# SCH001.net
KiCad netlist of a schematic drawn in Altium Designer
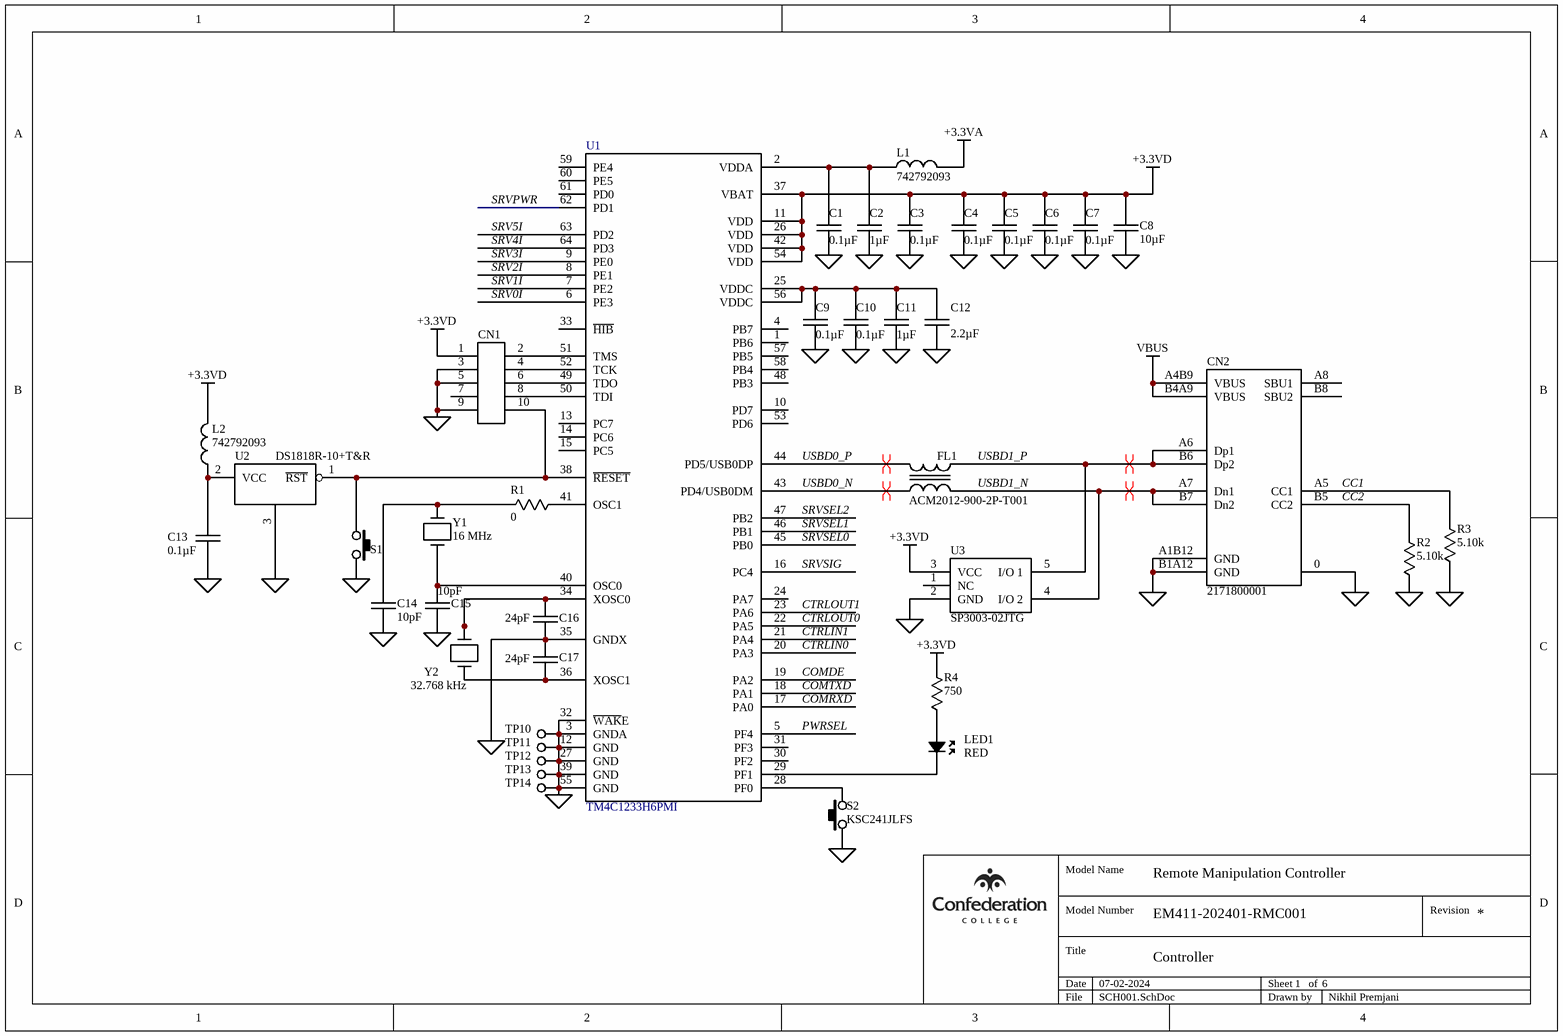
[diagram p0: SCH001.SchDoc]

(export (version "E")
  (design (tool "Eeschema 10.0.6"))
  (components
    (comp (ref "C1")
      (value "0.1µF")
      (footprint "CAPC2012X14N")
      (description "0.1µF/50V/±10% X7R Ceramic Chip Capacitor")
      (fields (field (name "MANUFACTURER") "Taiyo Yuden") (field (name "PARTNUMBER") "UMK212B7104KGHT"))
      (libsource (lib "EM411-202401-RMC001-001") (part "UMK212B7104KGHT"))
    )
    (comp (ref "C2")
      (value "1µF")
      (footprint "CAPC2012X14N")
      (description "1µF/50V/±10% X7R Ceramic Chip Capacitor")
      (fields
        (field (name "MANUFACTURER") "Samsung Electro-Mechanics")
        (field (name "PARTNUMBER") "CL21B105KBFNNNG")
      )
      (libsource (lib "EM411-202401-RMC001-001") (part "CL21B105KBFNNNG"))
    )
    (comp (ref "C3")
      (value "0.1µF")
      (footprint "CAPC2012X14N")
      (description "0.1µF/50V/±10% X7R Ceramic Chip Capacitor")
      (fields (field (name "MANUFACTURER") "Taiyo Yuden") (field (name "PARTNUMBER") "UMK212B7104KGHT"))
      (libsource (lib "EM411-202401-RMC001-001") (part "UMK212B7104KGHT"))
    )
    (comp (ref "C4")
      (value "0.1µF")
      (footprint "CAPC2012X14N")
      (description "0.1µF/50V/±10% X7R Ceramic Chip Capacitor")
      (fields (field (name "MANUFACTURER") "Taiyo Yuden") (field (name "PARTNUMBER") "UMK212B7104KGHT"))
      (libsource (lib "EM411-202401-RMC001-001") (part "UMK212B7104KGHT"))
    )
    (comp (ref "C5")
      (value "0.1µF")
      (footprint "CAPC2012X14N")
      (description "0.1µF/50V/±10% X7R Ceramic Chip Capacitor")
      (fields (field (name "MANUFACTURER") "Taiyo Yuden") (field (name "PARTNUMBER") "UMK212B7104KGHT"))
      (libsource (lib "EM411-202401-RMC001-001") (part "UMK212B7104KGHT"))
    )
    (comp (ref "C6")
      (value "0.1µF")
      (footprint "CAPC2012X14N")
      (description "0.1µF/50V/±10% X7R Ceramic Chip Capacitor")
      (fields (field (name "MANUFACTURER") "Taiyo Yuden") (field (name "PARTNUMBER") "UMK212B7104KGHT"))
      (libsource (lib "EM411-202401-RMC001-001") (part "UMK212B7104KGHT"))
    )
    (comp (ref "C7")
      (value "0.1µF")
      (footprint "CAPC2012X14N")
      (description "0.1µF/50V/±10% X7R Ceramic Chip Capacitor")
      (fields (field (name "MANUFACTURER") "Taiyo Yuden") (field (name "PARTNUMBER") "UMK212B7104KGHT"))
      (libsource (lib "EM411-202401-RMC001-001") (part "UMK212B7104KGHT"))
    )
    (comp (ref "C8")
      (value "10µF")
      (footprint "CAPC2012X14N")
      (description "10µF/25V 10% X5R Multi-Layer Ceramic Capacitor")
      (fields
        (field (name "MANUFACTURER") "Samsung Electro-Mechanics")
        (field (name "PARTNUMBER") "CL21A106KAFN3NE")
      )
      (libsource (lib "EM411-202401-RMC001-000-20240213-T10") (part "CL21A106KAFN3NE"))
    )
    (comp (ref "C9")
      (value "0.1µF")
      (footprint "CAPC2012X14N")
      (description "0.1µF/50V/±10% X7R Ceramic Chip Capacitor")
      (fields (field (name "MANUFACTURER") "Taiyo Yuden") (field (name "PARTNUMBER") "UMK212B7104KGHT"))
      (libsource (lib "EM411-202401-RMC001-001") (part "UMK212B7104KGHT"))
    )
    (comp (ref "C10")
      (value "0.1µF")
      (footprint "CAPC2012X14N")
      (description "0.1µF/50V/±10% X7R Ceramic Chip Capacitor")
      (fields (field (name "MANUFACTURER") "Taiyo Yuden") (field (name "PARTNUMBER") "UMK212B7104KGHT"))
      (libsource (lib "EM411-202401-RMC001-001") (part "UMK212B7104KGHT"))
    )
    (comp (ref "C11")
      (value "1µF")
      (footprint "CAPC2012X14N")
      (description "1µF/50V/±10% X7R Ceramic Chip Capacitor")
      (fields
        (field (name "MANUFACTURER") "Samsung Electro-Mechanics")
        (field (name "PARTNUMBER") "CL21B105KBFNNNG")
      )
      (libsource (lib "EM411-202401-RMC001-001") (part "CL21B105KBFNNNG"))
    )
    (comp (ref "C12")
      (value "2.2µF")
      (footprint "CAPC2012X14N")
      (description "2.2µF/50V/10% Multilayer Ceramic Chip Capacitor")
      (fields (field (name "MANUFACTURER") "Taiyo Yuden") (field (name "PARTNUMBER") "UMK212BB7225KG-T"))
      (libsource (lib "EM411-202401-RMC001-001") (part "UMK212BB7225KG-T"))
    )
    (comp (ref "C13")
      (value "0.1µF")
      (footprint "CAPC2012X14N")
      (description "0.1µF/50V/±10% X7R Ceramic Chip Capacitor")
      (fields (field (name "MANUFACTURER") "Taiyo Yuden") (field (name "PARTNUMBER") "UMK212B7104KGHT"))
      (libsource (lib "EM411-202401-RMC001-001") (part "UMK212B7104KGHT"))
    )
    (comp (ref "C14")
      (value "10pF")
      (footprint "CAPC2012X09N")
      (description "10pF/100V/±10% C0G (NP0) Ceramic Chip Capacitor")
      (fields (field (name "MANUFACTURER") "Kyocera/AVX") (field (name "PARTNUMBER") "08051A100KAT"))
      (libsource (lib "EM411-202401-RMC001-000-20240213-T10") (part "08051A100KAT"))
    )
    (comp (ref "C15")
      (value "10pF")
      (footprint "CAPC2012X09N")
      (description "10pF/100V/±10% C0G (NP0) Ceramic Chip Capacitor")
      (fields (field (name "MANUFACTURER") "Kyocera/AVX") (field (name "PARTNUMBER") "08051A100KAT"))
      (libsource (lib "EM411-202401-RMC001-000-20240213-T10") (part "08051A100KAT"))
    )
    (comp (ref "C16")
      (value "24pF")
      (footprint "CAPC2012X09N")
      (description "24pF/50V/±5% C0G (NP0) Ceramic Chip Capacitor")
      (fields (field (name "MANUFACTURER") "Kyocera/AVX") (field (name "PARTNUMBER") "08055A240JAT"))
      (libsource (lib "EM411-202401-RMC001-001") (part "08055A240JAT"))
    )
    (comp (ref "C17")
      (value "24pF")
      (footprint "CAPC2012X09N")
      (description "24pF/50V/±5% C0G (NP0) Ceramic Chip Capacitor")
      (fields (field (name "MANUFACTURER") "Kyocera/AVX") (field (name "PARTNUMBER") "08055A240JAT"))
      (libsource (lib "EM411-202401-RMC001-001") (part "08055A240JAT"))
    )
    (comp (ref "CN1")
      (value "GRPB052VWVN-RC")
      (footprint "SULLINS_GRPB052VWVN-RC")
      (description ".050\"[1.27mm] Contact Centers, Male Header")
      (fields (field (name "MANUFACTURER") "Sullins Connector Solutions, Inc."))
      (libsource (lib "EM411-202401-RMC001-001") (part "GRPB052VWVN-RC"))
    )
    (comp (ref "CN2")
      (value "2171800001")
      (footprint "MOLEX_2171800001")
      (fields (field (name "MANUFACTURER") "Molex"))
      (libsource (lib "EM411-202401-RMC001-000-20240213-T10") (part "2171800001"))
    )
    (comp (ref "FL1")
      (value "ACM2012-900-2P-T001")
      (footprint "LITTELFUSE_ACM2012-900-2P-T001")
      (description "Common Mode Filter")
      (fields (field (name "MANUFACTURER") "TDK"))
      (libsource (lib "EM411-202401-RMC001-000-20240213-T10") (part "ACM2012-900-2P-T001"))
    )
    (comp (ref "L1")
      (value "742792093")
      (footprint "INDC2012X11N")
      (description "Multilayer SMD Ferrite")
      (fields (field (name "MANUFACTURER") "Wurth Elektronik"))
      (libsource (lib "EM411-202401-RMC001-001") (part "742792093"))
    )
    (comp (ref "L2")
      (value "742792093")
      (footprint "INDC2012X11N")
      (description "Multilayer SMD Ferrite")
      (fields (field (name "MANUFACTURER") "Wurth Elektronik"))
      (libsource (lib "EM411-202401-RMC001-001") (part "742792093"))
    )
    (comp (ref "LED1")
      (value "RED")
      (footprint "LEDM3228X19N")
      (description "Micro LED, 597 Series, Red, SMD LED")
      (fields
        (field (name "PARTNUMBER") "597-3008-207F")
        (field (name "MANUFACTURER") "Dialight Corporation")
      )
      (libsource (lib "EM411-202401-RMC001-000-20240213-T10") (part "597-3008-207F"))
    )
    (comp (ref "R1")
      (value "0")
      (footprint "VISHAY_RESC2012X06N")
      (description "0, Jumper, Pulse Proof, High Power Thick Film Chip Resistor")
      (fields
        (field (name "MANUFACTURER") "Vishay Intertechnology")
        (field (name "PARTNUMBER") "CRCW08050000Z0EAHP")
      )
      (libsource (lib "EM411-202401-RMC001-001") (part "CRCW08050000Z0EAHP"))
    )
    (comp (ref "R2")
      (value "5.10k")
      (footprint "RESC2012X06N")
      (description "5.10k, 1%, 0.125W Thick Film Chip Resistor")
      (fields (field (name "MANUFACTURER") "Bourns") (field (name "PARTNUMBER") "CR0805-FX-4421ELF"))
      (libsource (lib "EM411-202401-RMC001-001") (part "CR0805-FX-5101ELF"))
    )
    (comp (ref "R3")
      (value "5.10k")
      (footprint "RESC2012X06N")
      (description "5.10k, 1%, 0.125W Thick Film Chip Resistor")
      (fields (field (name "MANUFACTURER") "Bourns") (field (name "PARTNUMBER") "CR0805-FX-4421ELF"))
      (libsource (lib "EM411-202401-RMC001-001") (part "CR0805-FX-5101ELF"))
    )
    (comp (ref "R4")
      (value "750")
      (footprint "RESC2012X06N")
      (description "750, 1%, 0.125W Thick Film Chip Resistor")
      (fields (field (name "MANUFACTURER") "Bourns") (field (name "PARTNUMBER") "CR0805-FX-7500ELF"))
      (libsource (lib "EM411-202401-RMC001-001") (part "CR0805-FX-7500ELF"))
    )
    (comp (ref "S1")
      (value "KSC241JLFS")
      (footprint "CK_KSC241JLFS")
      (description "KSC Series Sealed Tact Switch for SMT")
      (fields (field (name "MANUFACTURER") "C&K Components"))
      (libsource (lib "EM411-202401-RMC001-001") (part "KSC241JLFS"))
    )
    (comp (ref "S2")
      (value "KSC241JLFS")
      (footprint "CK_KSC241JLFS")
      (description "KSC Series Sealed Tact Switch for SMT")
      (fields (field (name "MANUFACTURER") "C&K Components"))
      (libsource (lib "") (part "KSC241JLFS_1"))
    )
    (comp (ref "TP10")
      (value "Test Point")
      (footprint "TP100")
      (description "Test Point, Surface Mount, 3 mm")
      (fields (field (name "MANUFACTURER") "Confederation College"))
      (libsource (lib "EM411-202401-RMC001-000-20240213-T10") (part "TP3"))
    )
    (comp (ref "TP11")
      (value "Test Point")
      (footprint "TP100")
      (description "Test Point, Surface Mount, 3 mm")
      (fields (field (name "MANUFACTURER") "Confederation College"))
      (libsource (lib "EM411-202401-RMC001-000-20240213-T10") (part "TP3"))
    )
    (comp (ref "TP12")
      (value "Test Point")
      (footprint "TP100")
      (description "Test Point, Surface Mount, 3 mm")
      (fields (field (name "MANUFACTURER") "Confederation College"))
      (libsource (lib "EM411-202401-RMC001-000-20240213-T10") (part "TP3"))
    )
    (comp (ref "TP13")
      (value "Test Point")
      (footprint "TP100")
      (description "Test Point, Surface Mount, 3 mm")
      (fields (field (name "MANUFACTURER") "Confederation College"))
      (libsource (lib "EM411-202401-RMC001-000-20240213-T10") (part "TP3"))
    )
    (comp (ref "TP14")
      (value "Test Point")
      (footprint "TP100")
      (description "Test Point, Surface Mount, 3 mm")
      (fields (field (name "MANUFACTURER") "Confederation College"))
      (libsource (lib "EM411-202401-RMC001-000-20240213-T10") (part "TP3"))
    )
    (comp (ref "U1")
      (value "TM4C1233H6PMI")
      (footprint "TSQFP50P1200X1200X145-64N")
      (description "Microcontroller")
      (fields (field (name "MANUFACTURER") "Texas Instruments"))
      (libsource (lib "EM411-202401-RMC001-000-20240213-T10") (part "TM4C1233H6PMI"))
    )
    (comp (ref "U2")
      (value "DS1818R-10+T&R")
      (footprint "SOT95P237X112-3N")
      (description "3.3 V EconoReset with Pushbutton")
      (fields (field (name "MANUFACTURER") "Maxim Integrated"))
      (libsource (lib "EM411-202401-RMC001-001") (part "DS1818R-10+T&R"))
    )
    (comp (ref "U3")
      (value "SP3003-02JTG")
      (footprint "SOT65P220X110-5N")
      (description "TVS Diode Array - Low Capacitance ESD Protection")
      (fields (field (name "MANUFACTURER") "Littelfuse"))
      (libsource (lib "EM411-202401-RMC001-001") (part "SP3003-02JTG"))
    )
    (comp (ref "Y1")
      (value "16 MHz")
      (footprint "ABRACON_ABM3")
      (description "16 MHz Miniature Ceramic SMD Crystal")
      (fields
        (field (name "PARTNUMBER") "ABM3-16.000MHZ-B2-T")
        (field (name "MANUFACTURER") "Abracon Corporation")
      )
      (libsource (lib "EM411-202401-RMC001-001") (part "ABM3-16.000MHZ-B2-T"))
    )
    (comp (ref "Y2")
      (value "32.768 kHz")
      (footprint "ABRACON_AB26TRB")
      (description "32.768 kHz Radial Can Crystal")
      (fields
        (field (name "PARTNUMBER") "AB26TRB-32.768KHZ-T")
        (field (name "MANUFACTURER") "Abracon Corporation")
      )
      (libsource (lib "EM411-202401-RMC001-001") (part "AB26TRB-32.768KHZ-T"))
    )
  )
  (nets
    (net (code "1") (name "+3.3VA") (class "Default")
      (node (ref "L1") (pin "2") (pinfunction "2_2") (pintype "passive"))
    )
    (net (code "2") (name "+3.3VD") (class "Default")
      (node (ref "C3") (pin "1") (pinfunction "1_1") (pintype "passive"))
      (node (ref "C4") (pin "1") (pinfunction "1_1") (pintype "passive"))
      (node (ref "C5") (pin "1") (pinfunction "1_1") (pintype "passive"))
      (node (ref "C6") (pin "1") (pinfunction "1_1") (pintype "passive"))
      (node (ref "C7") (pin "1") (pinfunction "1_1") (pintype "passive"))
      (node (ref "C8") (pin "1") (pinfunction "1_1") (pintype "passive"))
      (node (ref "CN1") (pin "1") (pinfunction "1_1") (pintype "passive"))
      (node (ref "L2") (pin "2") (pinfunction "2_2") (pintype "passive"))
      (node (ref "R4") (pin "2") (pinfunction "2_2") (pintype "passive"))
      (node (ref "U1") (pin "11") (pinfunction "VDD_11") (pintype "passive"))
      (node (ref "U1") (pin "26") (pinfunction "VDD_26") (pintype "passive"))
      (node (ref "U1") (pin "37") (pinfunction "VBAT_37") (pintype "passive"))
      (node (ref "U1") (pin "42") (pinfunction "VDD_42") (pintype "passive"))
      (node (ref "U1") (pin "54") (pinfunction "VDD_54") (pintype "passive"))
      (node (ref "U3") (pin "3") (pinfunction "VCC_3") (pintype "passive"))
    )
    (net (code "3") (name "/CC1") (class "Default")
      (node (ref "CN2") (pin "A5") (pinfunction "CC1_A5") (pintype "passive"))
      (node (ref "R3") (pin "2") (pinfunction "2_2") (pintype "passive"))
    )
    (net (code "4") (name "/CC2") (class "Default")
      (node (ref "CN2") (pin "B5") (pinfunction "CC2_B5") (pintype "passive"))
      (node (ref "R2") (pin "2") (pinfunction "2_2") (pintype "passive"))
    )
    (net (code "5") (name "/COMDE") (class "Default")
      (node (ref "U1") (pin "19") (pinfunction "PA2_19") (pintype "passive"))
    )
    (net (code "6") (name "/COMRXD") (class "Default")
      (node (ref "U1") (pin "17") (pinfunction "PA0_17") (pintype "passive"))
    )
    (net (code "7") (name "/COMTXD") (class "Default")
      (node (ref "U1") (pin "18") (pinfunction "PA1_18") (pintype "passive"))
    )
    (net (code "8") (name "/CTRLIN0") (class "Default")
      (node (ref "U1") (pin "20") (pinfunction "PA3_20") (pintype "passive"))
    )
    (net (code "9") (name "/CTRLIN1") (class "Default")
      (node (ref "U1") (pin "21") (pinfunction "PA4_21") (pintype "passive"))
    )
    (net (code "10") (name "/CTRLOUT0") (class "Default")
      (node (ref "U1") (pin "22") (pinfunction "PA5_22") (pintype "passive"))
    )
    (net (code "11") (name "/CTRLOUT1") (class "Default")
      (node (ref "U1") (pin "23") (pinfunction "PA6_23") (pintype "passive"))
    )
    (net (code "12") (name "/PWRSEL") (class "Default")
      (node (ref "U1") (pin "5") (pinfunction "PF4_5") (pintype "passive"))
    )
    (net (code "13") (name "/SRV0I") (class "Default")
      (node (ref "U1") (pin "6") (pinfunction "PE3_6") (pintype "passive"))
    )
    (net (code "14") (name "/SRV1I") (class "Default")
      (node (ref "U1") (pin "7") (pinfunction "PE2_7") (pintype "passive"))
    )
    (net (code "15") (name "/SRV2I") (class "Default")
      (node (ref "U1") (pin "8") (pinfunction "PE1_8") (pintype "passive"))
    )
    (net (code "16") (name "/SRV3I") (class "Default")
      (node (ref "U1") (pin "9") (pinfunction "PE0_9") (pintype "passive"))
    )
    (net (code "17") (name "/SRV4I") (class "Default")
      (node (ref "U1") (pin "64") (pinfunction "PD3_64") (pintype "passive"))
    )
    (net (code "18") (name "/SRV5I") (class "Default")
      (node (ref "U1") (pin "63") (pinfunction "PD2_63") (pintype "passive"))
    )
    (net (code "19") (name "/SRVPWR") (class "Default")
      (node (ref "U1") (pin "62") (pinfunction "PD1_62") (pintype "passive"))
    )
    (net (code "20") (name "/SRVSEL0") (class "Default")
      (node (ref "U1") (pin "45") (pinfunction "PB0_45") (pintype "passive"))
    )
    (net (code "21") (name "/SRVSEL1") (class "Default")
      (node (ref "U1") (pin "46") (pinfunction "PB1_46") (pintype "passive"))
    )
    (net (code "22") (name "/SRVSEL2") (class "Default")
      (node (ref "U1") (pin "47") (pinfunction "PB2_47") (pintype "passive"))
    )
    (net (code "23") (name "/SRVSIG") (class "Default")
      (node (ref "U1") (pin "16") (pinfunction "PC4_16") (pintype "passive"))
    )
    (net (code "24") (name "/USBD0_N") (class "Default")
      (node (ref "FL1") (pin "2") (pinfunction "2_2") (pintype "passive"))
      (node (ref "U1") (pin "43") (pinfunction "PD4/USB0DM_43") (pintype "passive"))
    )
    (net (code "25") (name "/USBD0_P") (class "Default")
      (node (ref "FL1") (pin "1") (pinfunction "1_1") (pintype "passive"))
      (node (ref "U1") (pin "44") (pinfunction "PD5/USB0DP_44") (pintype "passive"))
    )
    (net (code "26") (name "/USBD1_N") (class "Default")
      (node (ref "CN2") (pin "A7") (pinfunction "Dn1_A7") (pintype "passive"))
      (node (ref "CN2") (pin "B7") (pinfunction "Dn2_B7") (pintype "passive"))
      (node (ref "FL1") (pin "3") (pinfunction "3_3") (pintype "passive"))
      (node (ref "U3") (pin "4") (pinfunction "I/O_2_4") (pintype "passive"))
    )
    (net (code "27") (name "/USBD1_P") (class "Default")
      (node (ref "CN2") (pin "A6") (pinfunction "Dp1_A6") (pintype "passive"))
      (node (ref "CN2") (pin "B6") (pinfunction "Dp2_B6") (pintype "passive"))
      (node (ref "FL1") (pin "4") (pinfunction "4_4") (pintype "passive"))
      (node (ref "U3") (pin "5") (pinfunction "I/O_1_5") (pintype "passive"))
    )
    (net (code "28") (name "GND") (class "Default")
      (node (ref "C1") (pin "2") (pinfunction "2_2") (pintype "passive"))
      (node (ref "C10") (pin "2") (pinfunction "2_2") (pintype "passive"))
      (node (ref "C11") (pin "2") (pinfunction "2_2") (pintype "passive"))
      (node (ref "C12") (pin "2") (pinfunction "2_2") (pintype "passive"))
      (node (ref "C13") (pin "2") (pinfunction "2_2") (pintype "passive"))
      (node (ref "C14") (pin "2") (pinfunction "2_2") (pintype "passive"))
      (node (ref "C15") (pin "2") (pinfunction "2_2") (pintype "passive"))
      (node (ref "C16") (pin "2") (pinfunction "2_2") (pintype "passive"))
      (node (ref "C17") (pin "1") (pinfunction "1_1") (pintype "passive"))
      (node (ref "C2") (pin "2") (pinfunction "2_2") (pintype "passive"))
      (node (ref "C3") (pin "2") (pinfunction "2_2") (pintype "passive"))
      (node (ref "C4") (pin "2") (pinfunction "2_2") (pintype "passive"))
      (node (ref "C5") (pin "2") (pinfunction "2_2") (pintype "passive"))
      (node (ref "C6") (pin "2") (pinfunction "2_2") (pintype "passive"))
      (node (ref "C7") (pin "2") (pinfunction "2_2") (pintype "passive"))
      (node (ref "C8") (pin "2") (pinfunction "2_2") (pintype "passive"))
      (node (ref "C9") (pin "2") (pinfunction "2_2") (pintype "passive"))
      (node (ref "CN1") (pin "3") (pinfunction "3_3") (pintype "passive"))
      (node (ref "CN1") (pin "5") (pinfunction "5_5") (pintype "passive"))
      (node (ref "CN1") (pin "9") (pinfunction "9_9") (pintype "passive"))
      (node (ref "CN2") (pin "0") (pinfunction "0_0") (pintype "passive"))
      (node (ref "CN2") (pin "A1B12") (pinfunction "GND_A1B12") (pintype "passive"))
      (node (ref "CN2") (pin "B1A12") (pinfunction "GND_B1A12") (pintype "passive"))
      (node (ref "R2") (pin "1") (pinfunction "1_1") (pintype "passive"))
      (node (ref "R3") (pin "1") (pinfunction "1_1") (pintype "passive"))
      (node (ref "S1") (pin "1") (pinfunction "1_1") (pintype "passive"))
      (node (ref "S2") (pin "2") (pinfunction "2_2") (pintype "passive"))
      (node (ref "TP10") (pin "1") (pinfunction "1_1") (pintype "passive"))
      (node (ref "TP11") (pin "1") (pinfunction "1_1") (pintype "passive"))
      (node (ref "TP12") (pin "1") (pinfunction "1_1") (pintype "passive"))
      (node (ref "TP13") (pin "1") (pinfunction "1_1") (pintype "passive"))
      (node (ref "TP14") (pin "1") (pinfunction "1_1") (pintype "passive"))
      (node (ref "U1") (pin "12") (pinfunction "GND_12") (pintype "passive"))
      (node (ref "U1") (pin "27") (pinfunction "GND_27") (pintype "passive"))
      (node (ref "U1") (pin "3") (pinfunction "GNDA_3") (pintype "passive"))
      (node (ref "U1") (pin "32") (pinfunction "~{WAK}E_32") (pintype "passive"))
      (node (ref "U1") (pin "35") (pinfunction "GNDX_35") (pintype "passive"))
      (node (ref "U1") (pin "39") (pinfunction "GND_39") (pintype "passive"))
      (node (ref "U1") (pin "55") (pinfunction "GND_55") (pintype "passive"))
      (node (ref "U2") (pin "3") (pinfunction "GND_3") (pintype "power_in"))
      (node (ref "U3") (pin "2") (pinfunction "GND_2") (pintype "passive"))
    )
    (net (code "29") (name "Net-(C10-Pad1)") (class "Default")
      (node (ref "C10") (pin "1") (pinfunction "1_1") (pintype "passive"))
      (node (ref "C11") (pin "1") (pinfunction "1_1") (pintype "passive"))
      (node (ref "C12") (pin "1") (pinfunction "1_1") (pintype "passive"))
      (node (ref "C9") (pin "1") (pinfunction "1_1") (pintype "passive"))
      (node (ref "U1") (pin "25") (pinfunction "VDDC_25") (pintype "passive"))
      (node (ref "U1") (pin "56") (pinfunction "VDDC_56") (pintype "passive"))
    )
    (net (code "30") (name "Net-(C14-Pad1)") (class "Default")
      (node (ref "C14") (pin "1") (pinfunction "1_1") (pintype "passive"))
      (node (ref "R1") (pin "1") (pinfunction "1_1") (pintype "passive"))
      (node (ref "Y1") (pin "1") (pinfunction "1_1") (pintype "passive"))
    )
    (net (code "31") (name "Net-(LED1-PadA)") (class "Default")
      (node (ref "LED1") (pin "A") (pinfunction "A_A") (pintype "passive"))
      (node (ref "R4") (pin "1") (pinfunction "1_1") (pintype "passive"))
    )
    (net (code "32") (name "Net-(U1-OSC0)") (class "Default")
      (node (ref "C15") (pin "1") (pinfunction "1_1") (pintype "passive"))
      (node (ref "U1") (pin "40") (pinfunction "OSC0_40") (pintype "passive"))
      (node (ref "Y1") (pin "2") (pinfunction "2_2") (pintype "passive"))
    )
    (net (code "33") (name "Net-(U1-OSC1)") (class "Default")
      (node (ref "R1") (pin "2") (pinfunction "2_2") (pintype "passive"))
      (node (ref "U1") (pin "41") (pinfunction "OSC1_41") (pintype "passive"))
    )
    (net (code "34") (name "Net-(U1-PF0)") (class "Default")
      (node (ref "S2") (pin "1") (pinfunction "1_1") (pintype "passive"))
      (node (ref "U1") (pin "28") (pinfunction "PF0_28") (pintype "passive"))
    )
    (net (code "35") (name "Net-(U1-PF1)") (class "Default")
      (node (ref "LED1") (pin "K") (pinfunction "K_K") (pintype "passive"))
      (node (ref "U1") (pin "29") (pinfunction "PF1_29") (pintype "passive"))
    )
    (net (code "36") (name "Net-(U1-TCK)") (class "Default")
      (node (ref "CN1") (pin "4") (pinfunction "4_4") (pintype "passive"))
      (node (ref "U1") (pin "52") (pinfunction "TCK_52") (pintype "passive"))
    )
    (net (code "37") (name "Net-(U1-TDI)") (class "Default")
      (node (ref "CN1") (pin "8") (pinfunction "8_8") (pintype "passive"))
      (node (ref "U1") (pin "50") (pinfunction "TDI_50") (pintype "passive"))
    )
    (net (code "38") (name "Net-(U1-TDO)") (class "Default")
      (node (ref "CN1") (pin "6") (pinfunction "6_6") (pintype "passive"))
      (node (ref "U1") (pin "49") (pinfunction "TDO_49") (pintype "passive"))
    )
    (net (code "39") (name "Net-(U1-TMS)") (class "Default")
      (node (ref "CN1") (pin "2") (pinfunction "2_2") (pintype "passive"))
      (node (ref "U1") (pin "51") (pinfunction "TMS_51") (pintype "passive"))
    )
    (net (code "40") (name "Net-(U1-VDDA)") (class "Default")
      (node (ref "C1") (pin "1") (pinfunction "1_1") (pintype "passive"))
      (node (ref "C2") (pin "1") (pinfunction "1_1") (pintype "passive"))
      (node (ref "L1") (pin "1") (pinfunction "1_1") (pintype "passive"))
      (node (ref "U1") (pin "2") (pinfunction "VDDA_2") (pintype "passive"))
    )
    (net (code "41") (name "Net-(U1-XOSC0)") (class "Default")
      (node (ref "C16") (pin "1") (pinfunction "1_1") (pintype "passive"))
      (node (ref "U1") (pin "34") (pinfunction "XOSC0_34") (pintype "passive"))
      (node (ref "Y2") (pin "2") (pinfunction "2_2") (pintype "passive"))
    )
    (net (code "42") (name "Net-(U1-XOSC1)") (class "Default")
      (node (ref "C17") (pin "2") (pinfunction "2_2") (pintype "passive"))
      (node (ref "U1") (pin "36") (pinfunction "XOSC1_36") (pintype "passive"))
      (node (ref "Y2") (pin "1") (pinfunction "1_1") (pintype "passive"))
    )
    (net (code "43") (name "Net-(U1-~{RESET})") (class "Default")
      (node (ref "CN1") (pin "10") (pinfunction "10_10") (pintype "passive"))
      (node (ref "S1") (pin "2") (pinfunction "2_2") (pintype "passive"))
      (node (ref "U1") (pin "38") (pinfunction "~{RESET}_38") (pintype "passive"))
      (node (ref "U2") (pin "1") (pinfunction "~{RST}_1") (pintype "open_collector"))
    )
    (net (code "44") (name "Net-(U2-VCC)") (class "Default")
      (node (ref "C13") (pin "1") (pinfunction "1_1") (pintype "passive"))
      (node (ref "L2") (pin "1") (pinfunction "1_1") (pintype "passive"))
      (node (ref "U2") (pin "2") (pinfunction "VCC_2") (pintype "power_in"))
    )
    (net (code "45") (name "VBUS") (class "Default")
      (node (ref "CN2") (pin "A4B9") (pinfunction "VBUS_A4B9") (pintype "passive"))
      (node (ref "CN2") (pin "B4A9") (pinfunction "VBUS_B4A9") (pintype "passive"))
    )
    (net (code "46") (name "unconnected-(CN1-Pad7)") (class "Default")
      (node (ref "CN1") (pin "7") (pinfunction "7_7") (pintype "passive"))
    )
    (net (code "47") (name "unconnected-(CN2-SBU1-PadA8)") (class "Default")
      (node (ref "CN2") (pin "A8") (pinfunction "SBU1_A8") (pintype "passive"))
    )
    (net (code "48") (name "unconnected-(CN2-SBU2-PadB8)") (class "Default")
      (node (ref "CN2") (pin "B8") (pinfunction "SBU2_B8") (pintype "passive"))
    )
    (net (code "49") (name "unconnected-(U1-PA7-Pad24)") (class "Default")
      (node (ref "U1") (pin "24") (pinfunction "PA7_24") (pintype "passive"))
    )
    (net (code "50") (name "unconnected-(U1-PB3-Pad48)") (class "Default")
      (node (ref "U1") (pin "48") (pinfunction "PB3_48") (pintype "passive"))
    )
    (net (code "51") (name "unconnected-(U1-PB4-Pad58)") (class "Default")
      (node (ref "U1") (pin "58") (pinfunction "PB4_58") (pintype "passive"))
    )
    (net (code "52") (name "unconnected-(U1-PB5-Pad57)") (class "Default")
      (node (ref "U1") (pin "57") (pinfunction "PB5_57") (pintype "passive"))
    )
    (net (code "53") (name "unconnected-(U1-PB6-Pad1)") (class "Default")
      (node (ref "U1") (pin "1") (pinfunction "PB6_1") (pintype "passive"))
    )
    (net (code "54") (name "unconnected-(U1-PB7-Pad4)") (class "Default")
      (node (ref "U1") (pin "4") (pinfunction "PB7_4") (pintype "passive"))
    )
    (net (code "55") (name "unconnected-(U1-PC5-Pad15)") (class "Default")
      (node (ref "U1") (pin "15") (pinfunction "PC5_15") (pintype "passive"))
    )
    (net (code "56") (name "unconnected-(U1-PC6-Pad14)") (class "Default")
      (node (ref "U1") (pin "14") (pinfunction "PC6_14") (pintype "passive"))
    )
    (net (code "57") (name "unconnected-(U1-PC7-Pad13)") (class "Default")
      (node (ref "U1") (pin "13") (pinfunction "PC7_13") (pintype "passive"))
    )
    (net (code "58") (name "unconnected-(U1-PD0-Pad61)") (class "Default")
      (node (ref "U1") (pin "61") (pinfunction "PD0_61") (pintype "passive"))
    )
    (net (code "59") (name "unconnected-(U1-PD6-Pad53)") (class "Default")
      (node (ref "U1") (pin "53") (pinfunction "PD6_53") (pintype "passive"))
    )
    (net (code "60") (name "unconnected-(U1-PD7-Pad10)") (class "Default")
      (node (ref "U1") (pin "10") (pinfunction "PD7_10") (pintype "passive"))
    )
    (net (code "61") (name "unconnected-(U1-PE4-Pad59)") (class "Default")
      (node (ref "U1") (pin "59") (pinfunction "PE4_59") (pintype "passive"))
    )
    (net (code "62") (name "unconnected-(U1-PE5-Pad60)") (class "Default")
      (node (ref "U1") (pin "60") (pinfunction "PE5_60") (pintype "passive"))
    )
    (net (code "63") (name "unconnected-(U1-PF2-Pad30)") (class "Default")
      (node (ref "U1") (pin "30") (pinfunction "PF2_30") (pintype "passive"))
    )
    (net (code "64") (name "unconnected-(U1-PF3-Pad31)") (class "Default")
      (node (ref "U1") (pin "31") (pinfunction "PF3_31") (pintype "passive"))
    )
    (net (code "65") (name "unconnected-(U1-~{HIB}-Pad33)") (class "Default")
      (node (ref "U1") (pin "33") (pinfunction "~{HIB}_33") (pintype "passive"))
    )
    (net (code "66") (name "unconnected-(U3-NC-Pad1)") (class "Default")
      (node (ref "U3") (pin "1") (pinfunction "NC_1") (pintype "passive"))
    )
  )
)
